# EMI_Filter.net
KiCad netlist of a schematic drawn in Altium Designer
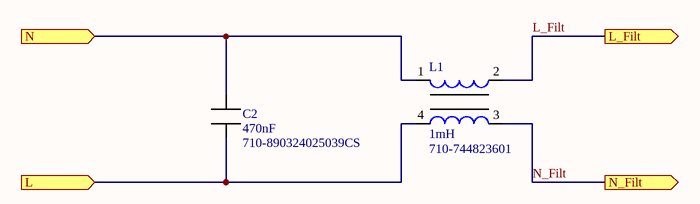
[diagram p0: EMI Filter.SchDoc]

(export (version "E")
  (design (tool "Eeschema 10.0.6"))
  (components
    (comp (ref "C2")
      (value "470nF")
      (footprint "890324025039CS")
      (description "Safety Capacitors WCAP-FTX2 20mm Lead 0.47uF 10% 275VAC")
      (fields (field (name "SUPPLIER PART NUMBER 1") "710-890324025039CS"))
      (libsource (lib "SMPS Schlib") (part "890324025039CS"))
    )
    (comp (ref "L1")
      (value "1mH")
      (footprint "744823601")
      (description "Common Mode Chokes / Filters WE-CMB Choke Type M 1mH 6A 13mOhm")
      (fields (field (name "SUPPLIER PART NUMBER 1") "710-744823601"))
      (libsource (lib "SMPS Schlib") (part "744823601"))
    )
  )
  (nets
    (net (code "1") (name "/L") (class "Default")
      (node (ref "C2") (pin "1") (pinfunction "1_1") (pintype "passive"))
      (node (ref "L1") (pin "4") (pinfunction "4_4") (pintype "passive"))
    )
    (net (code "2") (name "/L_Filt") (class "Default")
      (node (ref "L1") (pin "2") (pinfunction "2_2") (pintype "passive"))
    )
    (net (code "3") (name "/N") (class "Default")
      (node (ref "C2") (pin "2") (pinfunction "2_2") (pintype "passive"))
      (node (ref "L1") (pin "1") (pinfunction "1_1") (pintype "passive"))
    )
    (net (code "4") (name "/N_Filt") (class "Default")
      (node (ref "L1") (pin "3") (pinfunction "3_3") (pintype "passive"))
    )
  )
)
